# Pedal_System_Circuit.net
KiCad netlist of a schematic drawn in EAGLE
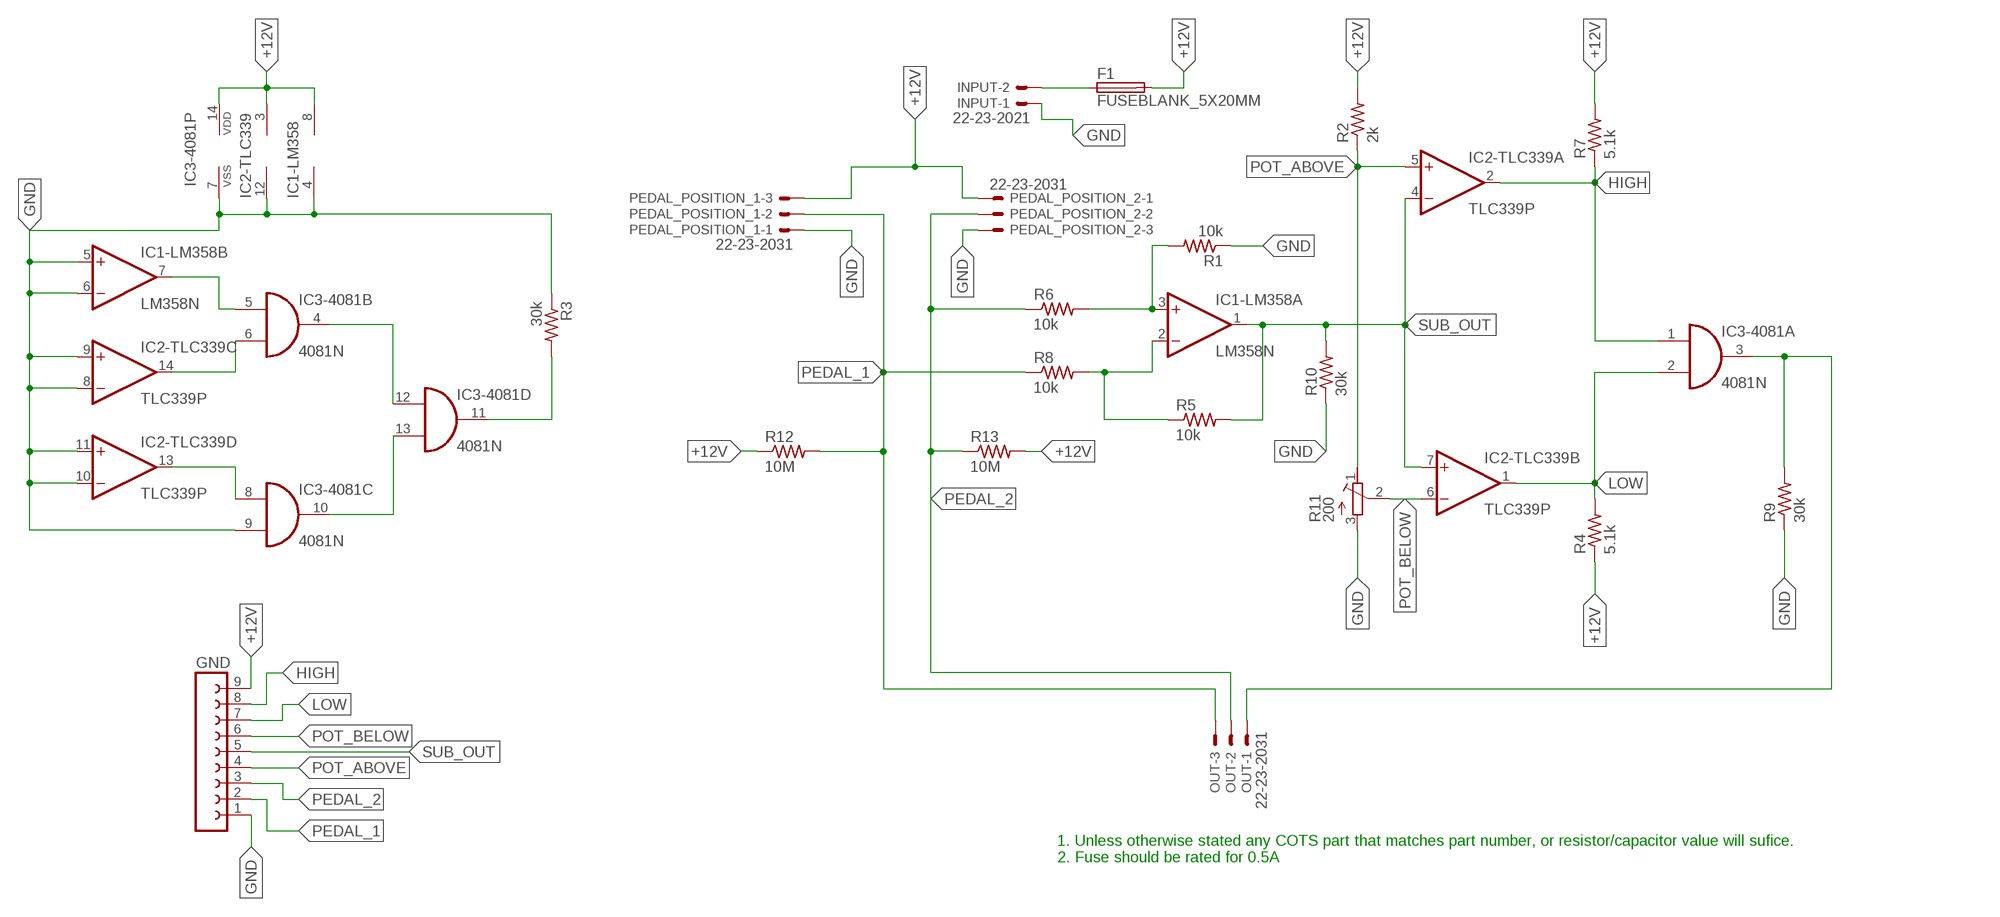
[diagram p0: schematic, sheet 1]

(export (version "E")
  (design (tool "Eeschema 10.0.6"))
  (components
    (comp (ref "F1")
      (value "FUSEBLANK_5X20MM")
      (footprint "eagle-import:FUSE_HOLDER_5X20MM")
      (libsource (lib "eagle-import") (part "FUSEBLANK_5X20MM"))
    )
    (comp (ref "GND")
      (value "FE09W")
      (footprint "eagle-import:FE09W")
      (libsource (lib "eagle-import") (part "FE09W"))
    )
    (comp (ref "IC1-LM358")
      (value "LM358N")
      (footprint "eagle-import:DIL08")
      (libsource (lib "eagle-import") (part "LM358N"))
    )
    (comp (ref "IC2-TLC339")
      (value "TLC339P")
      (footprint "eagle-import:DIL14")
      (libsource (lib "eagle-import") (part "TLC339P"))
    )
    (comp (ref "IC3-4081")
      (value "4081N")
      (footprint "eagle-import:DIL14")
      (libsource (lib "eagle-import") (part "4081N"))
    )
    (comp (ref "INPUT")
      (value "22-23-2021")
      (footprint "eagle-import:22-23-2021")
      (fields (field (name "MF") "MOLEX"))
      (libsource (lib "eagle-import") (part "22-23-2021"))
    )
    (comp (ref "OUT")
      (value "22-23-2031")
      (footprint "eagle-import:22-23-2031")
      (fields (field (name "MF") "MOLEX"))
      (libsource (lib "eagle-import") (part "22-23-2031"))
    )
    (comp (ref "PEDAL_POSITION_1")
      (value "22-23-2031")
      (footprint "eagle-import:22-23-2031")
      (fields (field (name "MF") "MOLEX"))
      (libsource (lib "eagle-import") (part "22-23-2031"))
    )
    (comp (ref "PEDAL_POSITION_2")
      (value "22-23-2031")
      (footprint "eagle-import:22-23-2031")
      (fields (field (name "MF") "MOLEX"))
      (libsource (lib "eagle-import") (part "22-23-2031"))
    )
    (comp (ref "R1")
      (value "10k")
      (footprint "eagle-import:0207_12")
      (libsource (lib "eagle-import") (part "R-US_0207/12"))
    )
    (comp (ref "R2")
      (value "2k")
      (footprint "eagle-import:0309_12")
      (libsource (lib "eagle-import") (part "R-US_0309/12"))
    )
    (comp (ref "R3")
      (value "30k")
      (footprint "eagle-import:0207_12")
      (libsource (lib "eagle-import") (part "R-US_0207/12"))
    )
    (comp (ref "R4")
      (value "5.1k")
      (footprint "eagle-import:0207_12")
      (libsource (lib "eagle-import") (part "R-US_0207/12"))
    )
    (comp (ref "R5")
      (value "10k")
      (footprint "eagle-import:0207_12")
      (libsource (lib "eagle-import") (part "R-US_0207/12"))
    )
    (comp (ref "R6")
      (value "10k")
      (footprint "eagle-import:0207_12")
      (libsource (lib "eagle-import") (part "R-US_0207/12"))
    )
    (comp (ref "R7")
      (value "5.1k")
      (footprint "eagle-import:0207_12")
      (libsource (lib "eagle-import") (part "R-US_0207/12"))
    )
    (comp (ref "R8")
      (value "10k")
      (footprint "eagle-import:0207_12")
      (libsource (lib "eagle-import") (part "R-US_0207/12"))
    )
    (comp (ref "R9")
      (value "30k")
      (footprint "eagle-import:0207_12")
      (libsource (lib "eagle-import") (part "R-US_0207/12"))
    )
    (comp (ref "R10")
      (value "30k")
      (footprint "eagle-import:0207_12")
      (libsource (lib "eagle-import") (part "R-US_0207/12"))
    )
    (comp (ref "R11")
      (value "200")
      (footprint "eagle-import:RTRIM43P")
      (libsource (lib "eagle-import") (part "R-TRIMM43P"))
    )
    (comp (ref "R12")
      (value "10M")
      (footprint "eagle-import:0207_12")
      (libsource (lib "eagle-import") (part "R-US_0207/12"))
    )
    (comp (ref "R13")
      (value "10M")
      (footprint "eagle-import:0207_12")
      (libsource (lib "eagle-import") (part "R-US_0207/12"))
    )
  )
  (nets
    (net (code "1") (name "+12V") (class "Default")
      (node (ref "F1") (pin "2") (pinfunction "2_2") (pintype "passive"))
      (node (ref "GND") (pin "9") (pinfunction "9_9") (pintype "passive"))
      (node (ref "IC1-LM358") (pin "8") (pinfunction "V+_8") (pintype "power_in"))
      (node (ref "IC2-TLC339") (pin "3") (pinfunction "V+_3") (pintype "power_in"))
      (node (ref "IC3-4081") (pin "14") (pinfunction "VDD_14") (pintype "power_in"))
      (node (ref "PEDAL_POSITION_1") (pin "3") (pinfunction "S_3") (pintype "passive"))
      (node (ref "PEDAL_POSITION_2") (pin "1") (pinfunction "S_1") (pintype "passive"))
      (node (ref "R12") (pin "1") (pinfunction "1_1") (pintype "passive"))
      (node (ref "R13") (pin "2") (pinfunction "2_2") (pintype "passive"))
      (node (ref "R2") (pin "2") (pinfunction "2_2") (pintype "passive"))
      (node (ref "R4") (pin "1") (pinfunction "1_1") (pintype "passive"))
      (node (ref "R7") (pin "2") (pinfunction "2_2") (pintype "passive"))
    )
    (net (code "2") (name "GND") (class "Default")
      (node (ref "GND") (pin "1") (pinfunction "1_1") (pintype "passive"))
      (node (ref "IC1-LM358") (pin "4") (pinfunction "V-_4") (pintype "power_in"))
      (node (ref "IC1-LM358") (pin "5") (pinfunction "+IN_5") (pintype "input"))
      (node (ref "IC1-LM358") (pin "6") (pinfunction "-IN_6") (pintype "input"))
      (node (ref "IC2-TLC339") (pin "10") (pinfunction "-IN_10") (pintype "input"))
      (node (ref "IC2-TLC339") (pin "11") (pinfunction "+IN_11") (pintype "input"))
      (node (ref "IC2-TLC339") (pin "12") (pinfunction "V-_12") (pintype "power_in"))
      (node (ref "IC2-TLC339") (pin "8") (pinfunction "-IN_8") (pintype "input"))
      (node (ref "IC2-TLC339") (pin "9") (pinfunction "+IN_9") (pintype "input"))
      (node (ref "IC3-4081") (pin "7") (pinfunction "VSS_7") (pintype "power_in"))
      (node (ref "IC3-4081") (pin "9") (pinfunction "I1_9") (pintype "input"))
      (node (ref "INPUT") (pin "1") (pinfunction "S_1") (pintype "passive"))
      (node (ref "PEDAL_POSITION_1") (pin "1") (pinfunction "S_1") (pintype "passive"))
      (node (ref "PEDAL_POSITION_2") (pin "3") (pinfunction "S_3") (pintype "passive"))
      (node (ref "R1") (pin "1") (pinfunction "1_1") (pintype "passive"))
      (node (ref "R10") (pin "1") (pinfunction "1_1") (pintype "passive"))
      (node (ref "R11") (pin "3") (pinfunction "A_3") (pintype "passive"))
      (node (ref "R3") (pin "1") (pinfunction "1_1") (pintype "passive"))
      (node (ref "R9") (pin "1") (pinfunction "1_1") (pintype "passive"))
    )
    (net (code "3") (name "HIGH") (class "Default")
      (node (ref "GND") (pin "8") (pinfunction "8_8") (pintype "passive"))
      (node (ref "IC2-TLC339") (pin "2") (pinfunction "OUT_2") (pintype "output"))
      (node (ref "IC3-4081") (pin "1") (pinfunction "I0_1") (pintype "input"))
      (node (ref "R7") (pin "1") (pinfunction "1_1") (pintype "passive"))
    )
    (net (code "4") (name "LOW") (class "Default")
      (node (ref "GND") (pin "7") (pinfunction "7_7") (pintype "passive"))
      (node (ref "IC2-TLC339") (pin "1") (pinfunction "OUT_1") (pintype "output"))
      (node (ref "IC3-4081") (pin "2") (pinfunction "I1_2") (pintype "input"))
      (node (ref "R4") (pin "2") (pinfunction "2_2") (pintype "passive"))
    )
    (net (code "5") (name "Net-(IC1-LM358A-+IN)") (class "Default")
      (node (ref "IC1-LM358") (pin "3") (pinfunction "+IN_3") (pintype "input"))
      (node (ref "R1") (pin "2") (pinfunction "2_2") (pintype "passive"))
      (node (ref "R6") (pin "2") (pinfunction "2_2") (pintype "passive"))
    )
    (net (code "6") (name "Net-(IC1-LM358A--IN)") (class "Default")
      (node (ref "IC1-LM358") (pin "2") (pinfunction "-IN_2") (pintype "input"))
      (node (ref "R5") (pin "1") (pinfunction "1_1") (pintype "passive"))
      (node (ref "R8") (pin "2") (pinfunction "2_2") (pintype "passive"))
    )
    (net (code "7") (name "Net-(IC1-LM358B-OUT)") (class "Default")
      (node (ref "IC1-LM358") (pin "7") (pinfunction "OUT_7") (pintype "output"))
      (node (ref "IC3-4081") (pin "5") (pinfunction "I0_5") (pintype "input"))
    )
    (net (code "8") (name "Net-(IC2-TLC339C-OUT)") (class "Default")
      (node (ref "IC2-TLC339") (pin "14") (pinfunction "OUT_14") (pintype "output"))
      (node (ref "IC3-4081") (pin "6") (pinfunction "I1_6") (pintype "input"))
    )
    (net (code "9") (name "Net-(IC2-TLC339D-OUT)") (class "Default")
      (node (ref "IC2-TLC339") (pin "13") (pinfunction "OUT_13") (pintype "output"))
      (node (ref "IC3-4081") (pin "8") (pinfunction "I0_8") (pintype "input"))
    )
    (net (code "10") (name "Net-(IC3-4081A-O)") (class "Default")
      (node (ref "IC3-4081") (pin "3") (pinfunction "O_3") (pintype "output"))
      (node (ref "OUT") (pin "1") (pinfunction "S_1") (pintype "passive"))
      (node (ref "R9") (pin "2") (pinfunction "2_2") (pintype "passive"))
    )
    (net (code "11") (name "Net-(IC3-4081B-O)") (class "Default")
      (node (ref "IC3-4081") (pin "12") (pinfunction "I0_12") (pintype "input"))
      (node (ref "IC3-4081") (pin "4") (pinfunction "O_4") (pintype "output"))
    )
    (net (code "12") (name "Net-(IC3-4081C-O)") (class "Default")
      (node (ref "IC3-4081") (pin "10") (pinfunction "O_10") (pintype "output"))
      (node (ref "IC3-4081") (pin "13") (pinfunction "I1_13") (pintype "input"))
    )
    (net (code "13") (name "Net-(IC3-4081D-O)") (class "Default")
      (node (ref "IC3-4081") (pin "11") (pinfunction "O_11") (pintype "output"))
      (node (ref "R3") (pin "2") (pinfunction "2_2") (pintype "passive"))
    )
    (net (code "14") (name "Net-(INPUTB-S)") (class "Default")
      (node (ref "F1") (pin "1") (pinfunction "1_1") (pintype "passive"))
      (node (ref "INPUT") (pin "2") (pinfunction "S_2") (pintype "passive"))
    )
    (net (code "15") (name "PEDAL_1") (class "Default")
      (node (ref "GND") (pin "2") (pinfunction "2_2") (pintype "passive"))
      (node (ref "OUT") (pin "3") (pinfunction "S_3") (pintype "passive"))
      (node (ref "PEDAL_POSITION_1") (pin "2") (pinfunction "S_2") (pintype "passive"))
      (node (ref "R12") (pin "2") (pinfunction "2_2") (pintype "passive"))
      (node (ref "R8") (pin "1") (pinfunction "1_1") (pintype "passive"))
    )
    (net (code "16") (name "PEDAL_2") (class "Default")
      (node (ref "GND") (pin "3") (pinfunction "3_3") (pintype "passive"))
      (node (ref "OUT") (pin "2") (pinfunction "S_2") (pintype "passive"))
      (node (ref "PEDAL_POSITION_2") (pin "2") (pinfunction "S_2") (pintype "passive"))
      (node (ref "R13") (pin "1") (pinfunction "1_1") (pintype "passive"))
      (node (ref "R6") (pin "1") (pinfunction "1_1") (pintype "passive"))
    )
    (net (code "17") (name "POT_ABOVE") (class "Default")
      (node (ref "GND") (pin "4") (pinfunction "4_4") (pintype "passive"))
      (node (ref "IC2-TLC339") (pin "5") (pinfunction "+IN_5") (pintype "input"))
      (node (ref "R11") (pin "1") (pinfunction "E_1") (pintype "passive"))
      (node (ref "R2") (pin "1") (pinfunction "1_1") (pintype "passive"))
    )
    (net (code "18") (name "POT_BELOW") (class "Default")
      (node (ref "GND") (pin "6") (pinfunction "6_6") (pintype "passive"))
      (node (ref "IC2-TLC339") (pin "6") (pinfunction "-IN_6") (pintype "input"))
      (node (ref "R11") (pin "2") (pinfunction "S_2") (pintype "passive"))
    )
    (net (code "19") (name "SUB_OUT") (class "Default")
      (node (ref "GND") (pin "5") (pinfunction "5_5") (pintype "passive"))
      (node (ref "IC1-LM358") (pin "1") (pinfunction "OUT_1") (pintype "output"))
      (node (ref "IC2-TLC339") (pin "4") (pinfunction "-IN_4") (pintype "input"))
      (node (ref "IC2-TLC339") (pin "7") (pinfunction "+IN_7") (pintype "input"))
      (node (ref "R10") (pin "2") (pinfunction "2_2") (pintype "passive"))
      (node (ref "R5") (pin "2") (pinfunction "2_2") (pintype "passive"))
    )
  )
)
